# helloworld.net
KiCad netlist of a schematic drawn in Altium Designer
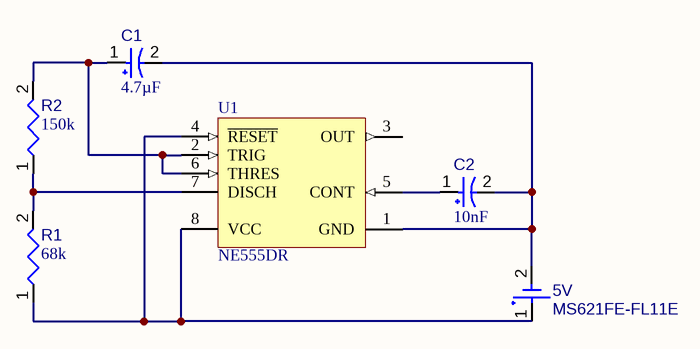
[diagram p0: helloworld.SchDoc]

(export (version "E")
  (design (tool "Eeschema 10.0.6"))
  (components
    (comp (ref "5V")
      (value "MS621FE-FL11E")
      (footprint "SEIK-MS621FE-FL11E-2_V")
      (description "MS Lihium Rechargeable Battery, 3 V, -20 to 60 degC, Tray")
      (libsource (lib "RVCC") (part "CMP-00622-2"))
    )
    (comp (ref "C1")
      (value "4.7µF")
      (footprint "CAPPR55-200-1100X500X1200")
      (description "Aluminum Electrolytic Capacitor, 1 uF, +/- 20%, 50 V, -55 to 105 degC, 2-Pin THD, RoHS, Bulk")
      (fields (field (name "TOLERANCE") "20%") (field (name "MANUFACTURER") "Panasonic"))
      (libsource (lib "RVCC") (part "CAP-P-2"))
    )
    (comp (ref "C2")
      (value "10nF")
      (footprint "CAPPR55-200-1100X500X1200")
      (description "Aluminum Electrolytic Capacitor, 1 uF, +/- 20%, 50 V, -55 to 105 degC, 2-Pin THD, RoHS, Bulk")
      (fields (field (name "TOLERANCE") "20%") (field (name "MANUFACTURER") "Panasonic"))
      (libsource (lib "RVCC") (part "CAP-P-2"))
    )
    (comp (ref "R1")
      (value "68k")
      (footprint "RESA86-1060X240")
      (description "Axial Resistor, 50 mOhm, +/- 1%, 2 W, -55 to 275 degC, 2-Pin THD, RoHS, Bulk")
      (fields (field (name "TOLERANCE") "1%") (field (name "POWER") "2W"))
      (libsource (lib "RVCC") (part "RES-2"))
    )
    (comp (ref "R2")
      (value "150k")
      (footprint "RESA86-1060X240")
      (description "Axial Resistor, 50 mOhm, +/- 1%, 2 W, -55 to 275 degC, 2-Pin THD, RoHS, Bulk")
      (fields (field (name "TOLERANCE") "1%") (field (name "POWER") "2W"))
      (libsource (lib "RVCC") (part "RES-2"))
    )
    (comp (ref "U1")
      (value "NE555DR")
      (footprint "D0008A_N")
      (description "Precision Timer, 4.5 to 16 V, 0 to 70 degC, 8-Pin SOIC (D), Green (RoHS & no Sb/Br), Tape and Reel")
      (fields (field (name "MANUFACTURER") "Texas Instruments"))
      (libsource (lib "RVCC") (part "TI-NE555-P-8"))
    )
  )
  (nets
    (net (code "1") (name "Net-(5V-+)") (class "Default")
      (node (ref "5V") (pin "1") (pinfunction "+_1") (pintype "passive"))
      (node (ref "R1") (pin "1") (pinfunction "1_1") (pintype "passive"))
      (node (ref "U1") (pin "4") (pinfunction "~{RESET}_4") (pintype "input"))
      (node (ref "U1") (pin "8") (pinfunction "VCC_8") (pintype "power_in"))
    )
    (net (code "2") (name "Net-(5V--)") (class "Default")
      (node (ref "5V") (pin "2") (pinfunction "-_2") (pintype "passive"))
      (node (ref "C1") (pin "2") (pinfunction "2_2") (pintype "passive"))
      (node (ref "C2") (pin "2") (pinfunction "2_2") (pintype "passive"))
      (node (ref "U1") (pin "1") (pinfunction "GND_1") (pintype "power_in"))
    )
    (net (code "3") (name "Net-(U1-CONT)") (class "Default")
      (node (ref "C2") (pin "1") (pinfunction "1_1") (pintype "passive"))
      (node (ref "U1") (pin "5") (pinfunction "CONT_5") (pintype "input"))
    )
    (net (code "4") (name "Net-(U1-DISCH)") (class "Default")
      (node (ref "R1") (pin "2") (pinfunction "2_2") (pintype "passive"))
      (node (ref "R2") (pin "1") (pinfunction "1_1") (pintype "passive"))
      (node (ref "U1") (pin "7") (pinfunction "DISCH_7") (pintype "open_collector"))
    )
    (net (code "5") (name "Net-(U1-THRES)") (class "Default")
      (node (ref "C1") (pin "1") (pinfunction "1_1") (pintype "passive"))
      (node (ref "R2") (pin "2") (pinfunction "2_2") (pintype "passive"))
      (node (ref "U1") (pin "2") (pinfunction "TRIG_2") (pintype "input"))
      (node (ref "U1") (pin "6") (pinfunction "THRES_6") (pintype "input"))
    )
    (net (code "6") (name "unconnected-(U1-OUT-Pad3)") (class "Default")
      (node (ref "U1") (pin "3") (pinfunction "OUT_3") (pintype "output"))
    )
  )
)
